# preamp.net
KiCad netlist of a schematic drawn in EAGLE
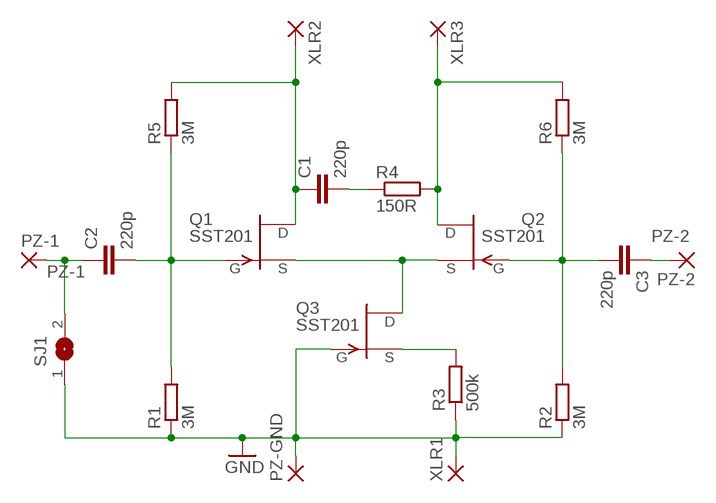
[diagram p0: schematic, sheet 1]

(export (version "E")
  (design (tool "Eeschema 10.0.6"))
  (components
    (comp (ref "C1")
      (value "220p")
      (footprint "eagle-import:C1206")
      (libsource (lib "eagle-import") (part "C-EUC1206"))
    )
    (comp (ref "C2")
      (value "220p")
      (footprint "eagle-import:C1206")
      (libsource (lib "eagle-import") (part "C-EUC1206"))
    )
    (comp (ref "C3")
      (value "220p")
      (footprint "eagle-import:C1206")
      (libsource (lib "eagle-import") (part "C-EUC1206"))
    )
    (comp (ref "PZ-1")
      (value "3,17/1,3")
      (footprint "eagle-import:3,17_1,3")
      (libsource (lib "eagle-import") (part "3,17/1,3"))
    )
    (comp (ref "PZ-2")
      (value "3,17/1,3")
      (footprint "eagle-import:3,17_1,3")
      (libsource (lib "eagle-import") (part "3,17/1,3"))
    )
    (comp (ref "PZ-GND")
      (value "3,17/1,3")
      (footprint "eagle-import:3,17_1,3")
      (libsource (lib "eagle-import") (part "3,17/1,3"))
    )
    (comp (ref "Q1")
      (value "SST201")
      (footprint "eagle-import:SOT23")
      (libsource (lib "eagle-import") (part "?20SST1"))
    )
    (comp (ref "Q2")
      (value "SST201")
      (footprint "eagle-import:SOT23")
      (libsource (lib "eagle-import") (part "?20SST1"))
    )
    (comp (ref "Q3")
      (value "SST201")
      (footprint "eagle-import:SOT23")
      (libsource (lib "eagle-import") (part "?20SST1"))
    )
    (comp (ref "R1")
      (value "3M")
      (footprint "eagle-import:R1206")
      (libsource (lib "eagle-import") (part "R-EU_R1206"))
    )
    (comp (ref "R2")
      (value "3M")
      (footprint "eagle-import:R1206")
      (libsource (lib "eagle-import") (part "R-EU_R1206"))
    )
    (comp (ref "R3")
      (value "500k")
      (footprint "eagle-import:R1206")
      (libsource (lib "eagle-import") (part "R-EU_R1206"))
    )
    (comp (ref "R4")
      (value "150R")
      (footprint "eagle-import:R1206")
      (libsource (lib "eagle-import") (part "R-EU_R1206"))
    )
    (comp (ref "R5")
      (value "3M")
      (footprint "eagle-import:R1206")
      (libsource (lib "eagle-import") (part "R-EU_R1206"))
    )
    (comp (ref "R6")
      (value "3M")
      (footprint "eagle-import:R1206")
      (libsource (lib "eagle-import") (part "R-EU_R1206"))
    )
    (comp (ref "SJ1") (value "SJ") (footprint "eagle-import:SJ") (libsource (lib "eagle-import") (part "SJ")))
    (comp (ref "XLR1")
      (value "3,17/1,3")
      (footprint "eagle-import:3,17_1,3")
      (libsource (lib "eagle-import") (part "3,17/1,3"))
    )
    (comp (ref "XLR2")
      (value "3,17/1,3")
      (footprint "eagle-import:3,17_1,3")
      (libsource (lib "eagle-import") (part "3,17/1,3"))
    )
    (comp (ref "XLR3")
      (value "3,17/1,3")
      (footprint "eagle-import:3,17_1,3")
      (libsource (lib "eagle-import") (part "3,17/1,3"))
    )
  )
  (nets
    (net (code "1") (name "/PZ-1") (class "Default")
      (node (ref "C2") (pin "1") (pinfunction "1_1") (pintype "passive"))
      (node (ref "PZ-1") (pin "1") (pinfunction "P_1") (pintype "passive"))
      (node (ref "SJ1") (pin "2") (pinfunction "2_2") (pintype "passive"))
    )
    (net (code "2") (name "/PZ-2") (class "Default")
      (node (ref "C3") (pin "1") (pinfunction "1_1") (pintype "passive"))
      (node (ref "PZ-2") (pin "1") (pinfunction "P_1") (pintype "passive"))
    )
    (net (code "3") (name "GND") (class "Default")
      (node (ref "PZ-GND") (pin "1") (pinfunction "P_1") (pintype "passive"))
      (node (ref "Q3") (pin "3") (pinfunction "G_3") (pintype "passive"))
      (node (ref "R1") (pin "1") (pinfunction "1_1") (pintype "passive"))
      (node (ref "R2") (pin "1") (pinfunction "1_1") (pintype "passive"))
      (node (ref "R3") (pin "1") (pinfunction "1_1") (pintype "passive"))
      (node (ref "SJ1") (pin "1") (pinfunction "1_1") (pintype "passive"))
      (node (ref "XLR1") (pin "1") (pinfunction "P_1") (pintype "passive"))
    )
    (net (code "4") (name "Net-(C1-Pad2)") (class "Default")
      (node (ref "C1") (pin "2") (pinfunction "2_2") (pintype "passive"))
      (node (ref "R4") (pin "1") (pinfunction "1_1") (pintype "passive"))
    )
    (net (code "5") (name "Net-(Q1-D)") (class "Default")
      (node (ref "C1") (pin "1") (pinfunction "1_1") (pintype "passive"))
      (node (ref "Q1") (pin "1") (pinfunction "D_1") (pintype "passive"))
      (node (ref "R5") (pin "2") (pinfunction "2_2") (pintype "passive"))
      (node (ref "XLR2") (pin "1") (pinfunction "P_1") (pintype "passive"))
    )
    (net (code "6") (name "Net-(Q1-G)") (class "Default")
      (node (ref "C2") (pin "2") (pinfunction "2_2") (pintype "passive"))
      (node (ref "Q1") (pin "3") (pinfunction "G_3") (pintype "passive"))
      (node (ref "R1") (pin "2") (pinfunction "2_2") (pintype "passive"))
      (node (ref "R5") (pin "1") (pinfunction "1_1") (pintype "passive"))
    )
    (net (code "7") (name "Net-(Q1-S)") (class "Default")
      (node (ref "Q1") (pin "2") (pinfunction "S_2") (pintype "passive"))
      (node (ref "Q2") (pin "2") (pinfunction "S_2") (pintype "passive"))
      (node (ref "Q3") (pin "1") (pinfunction "D_1") (pintype "passive"))
    )
    (net (code "8") (name "Net-(Q2-D)") (class "Default")
      (node (ref "Q2") (pin "1") (pinfunction "D_1") (pintype "passive"))
      (node (ref "R4") (pin "2") (pinfunction "2_2") (pintype "passive"))
      (node (ref "R6") (pin "2") (pinfunction "2_2") (pintype "passive"))
      (node (ref "XLR3") (pin "1") (pinfunction "P_1") (pintype "passive"))
    )
    (net (code "9") (name "Net-(Q2-G)") (class "Default")
      (node (ref "C3") (pin "2") (pinfunction "2_2") (pintype "passive"))
      (node (ref "Q2") (pin "3") (pinfunction "G_3") (pintype "passive"))
      (node (ref "R2") (pin "2") (pinfunction "2_2") (pintype "passive"))
      (node (ref "R6") (pin "1") (pinfunction "1_1") (pintype "passive"))
    )
    (net (code "10") (name "Net-(Q3-S)") (class "Default")
      (node (ref "Q3") (pin "2") (pinfunction "S_2") (pintype "passive"))
      (node (ref "R3") (pin "2") (pinfunction "2_2") (pintype "passive"))
    )
  )
)
